# schematic_final_wish.net
KiCad netlist of a schematic drawn in Altium Designer
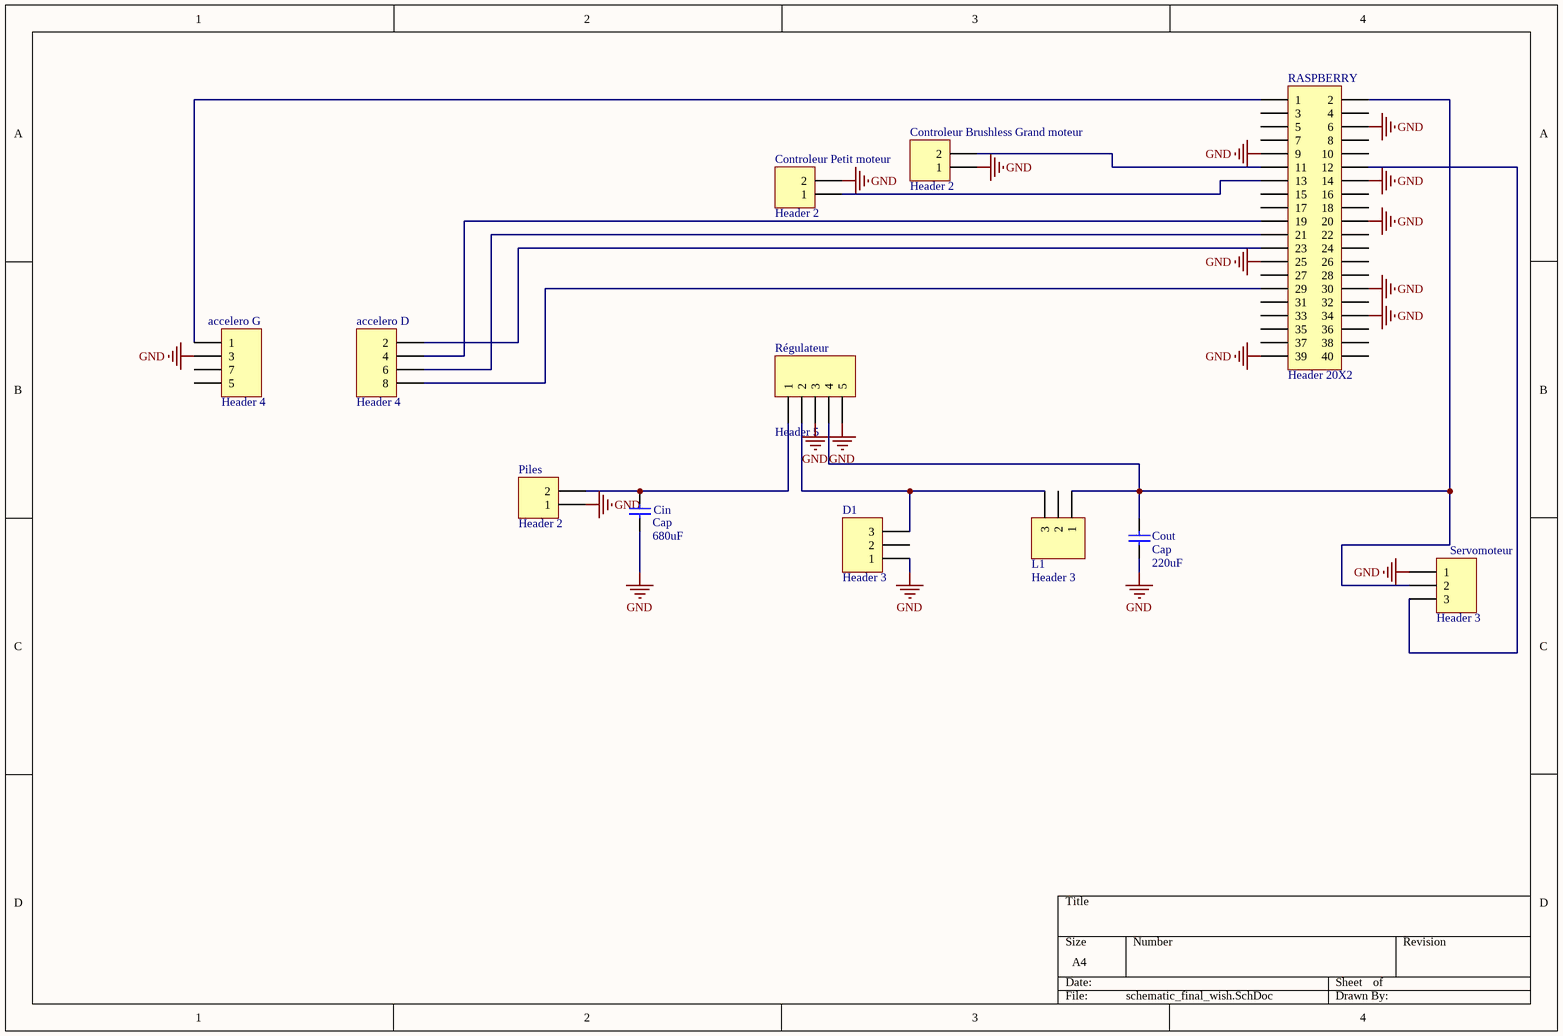
[diagram p0: schematic_final_wish.SchDoc]

(export (version "E")
  (design (tool "Eeschema 10.0.6"))
  (components
    (comp (ref "accelero D")
      (value "Header 4")
      (footprint "HDR1X4")
      (description "Header, 4-Pin")
      (fields (field (name "PUBLISHER") "Altium Limited"))
      (libsource (lib "") (part "Header 4_1"))
    )
    (comp (ref "accelero G")
      (value "Header 4")
      (footprint "HDR1X4")
      (description "Header, 4-Pin")
      (fields (field (name "PUBLISHER") "Altium Limited"))
      (libsource (lib "Miscellaneous Connectors") (part "Header 4"))
    )
    (comp (ref "Cin")
      (value "Cap")
      (footprint "RAD-0.3")
      (description "Capacitor")
      (fields (field (name "ALTIUM_VALUE") "680uF") (field (name "PUBLISHER") "Altium Limited"))
      (libsource (lib "Miscellaneous Devices") (part "Cap"))
    )
    (comp (ref "Controleur Brushless Grand moteur")
      (value "Header 2")
      (footprint "HDR1X2")
      (description "Header, 2-Pin")
      (fields (field (name "PUBLISHER") "Altium Limited"))
      (libsource (lib "Miscellaneous Connectors") (part "Header 2"))
    )
    (comp (ref "Controleur Petit moteur")
      (value "Header 2")
      (footprint "HDR1X2")
      (description "Header, 2-Pin")
      (fields (field (name "PUBLISHER") "Altium Limited"))
      (libsource (lib "Miscellaneous Connectors") (part "Header 2"))
    )
    (comp (ref "Cout")
      (value "Cap")
      (footprint "RAD-0.3")
      (description "Capacitor")
      (fields (field (name "ALTIUM_VALUE") "220uF") (field (name "PUBLISHER") "Altium Limited"))
      (libsource (lib "Miscellaneous Devices") (part "Cap"))
    )
    (comp (ref "D1")
      (value "Header 3")
      (footprint "HDR1X3")
      (description "Header, 3-Pin")
      (fields (field (name "PUBLISHER") "Altium Limited"))
      (libsource (lib "") (part "Header 3_2"))
    )
    (comp (ref "L1")
      (value "Header 3")
      (footprint "HDR1X3")
      (description "Header, 3-Pin")
      (fields (field (name "PUBLISHER") "Altium Limited"))
      (libsource (lib "") (part "Header 3_1"))
    )
    (comp (ref "Piles")
      (value "Header 2")
      (footprint "HDR1X2")
      (description "Header, 2-Pin")
      (fields (field (name "PUBLISHER") "Altium Limited"))
      (libsource (lib "Miscellaneous Connectors") (part "Header 2"))
    )
    (comp (ref "RASPBERRY")
      (value "Header 20X2")
      (footprint "HDR2X20")
      (description "Header, 20-Pin, Dual row")
      (fields (field (name "PUBLISHER") "Altium Limited"))
      (libsource (lib "Miscellaneous Connectors") (part "Header 20X2"))
    )
    (comp (ref "Régulateur")
      (value "Header 5")
      (footprint "HDR1X5")
      (description "Header, 5-Pin")
      (fields (field (name "PUBLISHER") "Altium Limited"))
      (libsource (lib "Miscellaneous Connectors") (part "Header 5"))
    )
    (comp (ref "Servomoteur")
      (value "Header 3")
      (footprint "HDR1X3")
      (description "Header, 3-Pin")
      (fields (field (name "PUBLISHER") "Altium Limited"))
      (libsource (lib "Miscellaneous Connectors") (part "Header 3"))
    )
  )
  (nets
    (net (code "1") (name "GND") (class "Default")
      (node (ref "Cin") (pin "2") (pinfunction "2_2") (pintype "passive"))
      (node (ref "Controleur Brushless Grand moteur") (pin "1") (pinfunction "1_1") (pintype "passive"))
      (node (ref "Controleur Petit moteur") (pin "2") (pinfunction "2_2") (pintype "passive"))
      (node (ref "Cout") (pin "2") (pinfunction "2_2") (pintype "passive"))
      (node (ref "D1") (pin "1") (pinfunction "1_1") (pintype "passive"))
      (node (ref "Piles") (pin "1") (pinfunction "1_1") (pintype "passive"))
      (node (ref "RASPBERRY") (pin "14") (pinfunction "14_14") (pintype "passive"))
      (node (ref "RASPBERRY") (pin "20") (pinfunction "20_20") (pintype "passive"))
      (node (ref "RASPBERRY") (pin "25") (pinfunction "25_25") (pintype "passive"))
      (node (ref "RASPBERRY") (pin "30") (pinfunction "30_30") (pintype "passive"))
      (node (ref "RASPBERRY") (pin "34") (pinfunction "34_34") (pintype "passive"))
      (node (ref "RASPBERRY") (pin "39") (pinfunction "39_39") (pintype "passive"))
      (node (ref "RASPBERRY") (pin "6") (pinfunction "6_6") (pintype "passive"))
      (node (ref "RASPBERRY") (pin "9") (pinfunction "9_9") (pintype "passive"))
      (node (ref "Régulateur") (pin "3") (pinfunction "3_3") (pintype "passive"))
      (node (ref "Régulateur") (pin "5") (pinfunction "5_5") (pintype "passive"))
      (node (ref "Servomoteur") (pin "1") (pinfunction "1_1") (pintype "passive"))
      (node (ref "accelero G") (pin "3") (pinfunction "3_3") (pintype "passive"))
    )
    (net (code "2") (name "Net-(Cin-Pad1)") (class "Default")
      (node (ref "Cin") (pin "1") (pinfunction "1_1") (pintype "passive"))
      (node (ref "Piles") (pin "2") (pinfunction "2_2") (pintype "passive"))
      (node (ref "Régulateur") (pin "1") (pinfunction "1_1") (pintype "passive"))
    )
    (net (code "3") (name "Net-(Controleur Brushless Grand moteur-Pad2)") (class "Default")
      (node (ref "Controleur Brushless Grand moteur") (pin "2") (pinfunction "2_2") (pintype "passive"))
      (node (ref "RASPBERRY") (pin "11") (pinfunction "11_11") (pintype "passive"))
    )
    (net (code "4") (name "Net-(Controleur Petit moteur-Pad1)") (class "Default")
      (node (ref "Controleur Petit moteur") (pin "1") (pinfunction "1_1") (pintype "passive"))
      (node (ref "RASPBERRY") (pin "13") (pinfunction "13_13") (pintype "passive"))
    )
    (net (code "5") (name "Net-(Cout-Pad1)") (class "Default")
      (node (ref "Cout") (pin "1") (pinfunction "1_1") (pintype "passive"))
      (node (ref "L1") (pin "1") (pinfunction "1_1") (pintype "passive"))
      (node (ref "RASPBERRY") (pin "2") (pinfunction "2_2") (pintype "passive"))
      (node (ref "Régulateur") (pin "4") (pinfunction "4_4") (pintype "passive"))
      (node (ref "Servomoteur") (pin "2") (pinfunction "2_2") (pintype "passive"))
    )
    (net (code "6") (name "Net-(D1-Pad3)") (class "Default")
      (node (ref "D1") (pin "3") (pinfunction "3_3") (pintype "passive"))
      (node (ref "L1") (pin "3") (pinfunction "3_3") (pintype "passive"))
      (node (ref "Régulateur") (pin "2") (pinfunction "2_2") (pintype "passive"))
    )
    (net (code "7") (name "Net-(RASPBERRY-Pad1)") (class "Default")
      (node (ref "RASPBERRY") (pin "1") (pinfunction "1_1") (pintype "passive"))
      (node (ref "accelero G") (pin "1") (pinfunction "1_1") (pintype "passive"))
    )
    (net (code "8") (name "Net-(RASPBERRY-Pad12)") (class "Default")
      (node (ref "RASPBERRY") (pin "12") (pinfunction "12_12") (pintype "passive"))
      (node (ref "Servomoteur") (pin "3") (pinfunction "3_3") (pintype "passive"))
    )
    (net (code "9") (name "Net-(RASPBERRY-Pad19)") (class "Default")
      (node (ref "RASPBERRY") (pin "19") (pinfunction "19_19") (pintype "passive"))
      (node (ref "accelero D") (pin "4") (pinfunction "4_4") (pintype "passive"))
    )
    (net (code "10") (name "Net-(RASPBERRY-Pad21)") (class "Default")
      (node (ref "RASPBERRY") (pin "21") (pinfunction "21_21") (pintype "passive"))
      (node (ref "accelero D") (pin "6") (pinfunction "6_6") (pintype "passive"))
    )
    (net (code "11") (name "Net-(RASPBERRY-Pad23)") (class "Default")
      (node (ref "RASPBERRY") (pin "23") (pinfunction "23_23") (pintype "passive"))
      (node (ref "accelero D") (pin "2") (pinfunction "2_2") (pintype "passive"))
    )
    (net (code "12") (name "Net-(RASPBERRY-Pad29)") (class "Default")
      (node (ref "RASPBERRY") (pin "29") (pinfunction "29_29") (pintype "passive"))
      (node (ref "accelero D") (pin "8") (pinfunction "8_8") (pintype "passive"))
    )
    (net (code "13") (name "unconnected-(D1-Pad2)") (class "Default")
      (node (ref "D1") (pin "2") (pinfunction "2_2") (pintype "passive"))
    )
    (net (code "14") (name "unconnected-(L1-Pad2)") (class "Default")
      (node (ref "L1") (pin "2") (pinfunction "2_2") (pintype "passive"))
    )
    (net (code "15") (name "unconnected-(RASPBERRY-Pad3)") (class "Default")
      (node (ref "RASPBERRY") (pin "3") (pinfunction "3_3") (pintype "passive"))
    )
    (net (code "16") (name "unconnected-(RASPBERRY-Pad4)") (class "Default")
      (node (ref "RASPBERRY") (pin "4") (pinfunction "4_4") (pintype "passive"))
    )
    (net (code "17") (name "unconnected-(RASPBERRY-Pad5)") (class "Default")
      (node (ref "RASPBERRY") (pin "5") (pinfunction "5_5") (pintype "passive"))
    )
    (net (code "18") (name "unconnected-(RASPBERRY-Pad7)") (class "Default")
      (node (ref "RASPBERRY") (pin "7") (pinfunction "7_7") (pintype "passive"))
    )
    (net (code "19") (name "unconnected-(RASPBERRY-Pad8)") (class "Default")
      (node (ref "RASPBERRY") (pin "8") (pinfunction "8_8") (pintype "passive"))
    )
    (net (code "20") (name "unconnected-(RASPBERRY-Pad10)") (class "Default")
      (node (ref "RASPBERRY") (pin "10") (pinfunction "10_10") (pintype "passive"))
    )
    (net (code "21") (name "unconnected-(RASPBERRY-Pad15)") (class "Default")
      (node (ref "RASPBERRY") (pin "15") (pinfunction "15_15") (pintype "passive"))
    )
    (net (code "22") (name "unconnected-(RASPBERRY-Pad16)") (class "Default")
      (node (ref "RASPBERRY") (pin "16") (pinfunction "16_16") (pintype "passive"))
    )
    (net (code "23") (name "unconnected-(RASPBERRY-Pad17)") (class "Default")
      (node (ref "RASPBERRY") (pin "17") (pinfunction "17_17") (pintype "passive"))
    )
    (net (code "24") (name "unconnected-(RASPBERRY-Pad18)") (class "Default")
      (node (ref "RASPBERRY") (pin "18") (pinfunction "18_18") (pintype "passive"))
    )
    (net (code "25") (name "unconnected-(RASPBERRY-Pad22)") (class "Default")
      (node (ref "RASPBERRY") (pin "22") (pinfunction "22_22") (pintype "passive"))
    )
    (net (code "26") (name "unconnected-(RASPBERRY-Pad24)") (class "Default")
      (node (ref "RASPBERRY") (pin "24") (pinfunction "24_24") (pintype "passive"))
    )
    (net (code "27") (name "unconnected-(RASPBERRY-Pad26)") (class "Default")
      (node (ref "RASPBERRY") (pin "26") (pinfunction "26_26") (pintype "passive"))
    )
    (net (code "28") (name "unconnected-(RASPBERRY-Pad27)") (class "Default")
      (node (ref "RASPBERRY") (pin "27") (pinfunction "27_27") (pintype "passive"))
    )
    (net (code "29") (name "unconnected-(RASPBERRY-Pad28)") (class "Default")
      (node (ref "RASPBERRY") (pin "28") (pinfunction "28_28") (pintype "passive"))
    )
    (net (code "30") (name "unconnected-(RASPBERRY-Pad31)") (class "Default")
      (node (ref "RASPBERRY") (pin "31") (pinfunction "31_31") (pintype "passive"))
    )
    (net (code "31") (name "unconnected-(RASPBERRY-Pad32)") (class "Default")
      (node (ref "RASPBERRY") (pin "32") (pinfunction "32_32") (pintype "passive"))
    )
    (net (code "32") (name "unconnected-(RASPBERRY-Pad33)") (class "Default")
      (node (ref "RASPBERRY") (pin "33") (pinfunction "33_33") (pintype "passive"))
    )
    (net (code "33") (name "unconnected-(RASPBERRY-Pad35)") (class "Default")
      (node (ref "RASPBERRY") (pin "35") (pinfunction "35_35") (pintype "passive"))
    )
    (net (code "34") (name "unconnected-(RASPBERRY-Pad36)") (class "Default")
      (node (ref "RASPBERRY") (pin "36") (pinfunction "36_36") (pintype "passive"))
    )
    (net (code "35") (name "unconnected-(RASPBERRY-Pad37)") (class "Default")
      (node (ref "RASPBERRY") (pin "37") (pinfunction "37_37") (pintype "passive"))
    )
    (net (code "36") (name "unconnected-(RASPBERRY-Pad38)") (class "Default")
      (node (ref "RASPBERRY") (pin "38") (pinfunction "38_38") (pintype "passive"))
    )
    (net (code "37") (name "unconnected-(RASPBERRY-Pad40)") (class "Default")
      (node (ref "RASPBERRY") (pin "40") (pinfunction "40_40") (pintype "passive"))
    )
    (net (code "38") (name "unconnected-(accelero G-Pad5)") (class "Default")
      (node (ref "accelero G") (pin "5") (pinfunction "5_5") (pintype "passive"))
    )
    (net (code "39") (name "unconnected-(accelero G-Pad7)") (class "Default")
      (node (ref "accelero G") (pin "7") (pinfunction "7_7") (pintype "passive"))
    )
  )
)
